# EV_SH.net
KiCad netlist of a schematic drawn in Altium Designer
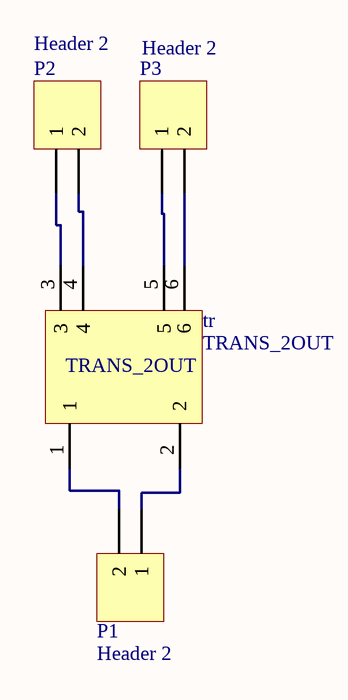
[diagram p0: EV_SH.SchDoc]

(export (version "E")
  (design (tool "Eeschema 10.0.6"))
  (components
    (comp (ref "P1")
      (value "Header 2")
      (footprint "HDR1X2")
      (description "Header, 2-Pin")
      (fields (field (name "PUBLISHER") "Altium Limited"))
      (libsource (lib "Miscellaneous Connectors") (part "Header 2"))
    )
    (comp (ref "P2")
      (value "Header 2")
      (footprint "HDR1X2")
      (description "Header, 2-Pin")
      (fields (field (name "PUBLISHER") "Altium Limited"))
      (libsource (lib "") (part "Header 2_1"))
    )
    (comp (ref "P3")
      (value "Header 2")
      (footprint "HDR1X2")
      (description "Header, 2-Pin")
      (fields (field (name "PUBLISHER") "Altium Limited"))
      (libsource (lib "") (part "Header 2_1"))
    )
    (comp (ref "tr")
      (value "TRANS_2OUT")
      (footprint "TRANS_2OUT")
      (libsource (lib "TRANS_LIB") (part "TRANS_2OUT"))
    )
  )
  (nets
    (net (code "1") (name "Net-(P1-Pad1)") (class "Default")
      (node (ref "P1") (pin "1") (pinfunction "1_1") (pintype "passive"))
      (node (ref "tr") (pin "2") (pinfunction "2_2") (pintype "passive"))
    )
    (net (code "2") (name "Net-(P1-Pad2)") (class "Default")
      (node (ref "P1") (pin "2") (pinfunction "2_2") (pintype "passive"))
      (node (ref "tr") (pin "1") (pinfunction "1_1") (pintype "passive"))
    )
    (net (code "3") (name "Net-(P2-Pad1)") (class "Default")
      (node (ref "P2") (pin "1") (pinfunction "1_1") (pintype "passive"))
      (node (ref "tr") (pin "3") (pinfunction "3_3") (pintype "passive"))
    )
    (net (code "4") (name "Net-(P2-Pad2)") (class "Default")
      (node (ref "P2") (pin "2") (pinfunction "2_2") (pintype "passive"))
      (node (ref "tr") (pin "4") (pinfunction "4_4") (pintype "passive"))
    )
    (net (code "5") (name "Net-(P3-Pad1)") (class "Default")
      (node (ref "P3") (pin "1") (pinfunction "1_1") (pintype "passive"))
      (node (ref "tr") (pin "5") (pinfunction "5_5") (pintype "passive"))
    )
    (net (code "6") (name "Net-(P3-Pad2)") (class "Default")
      (node (ref "P3") (pin "2") (pinfunction "2_2") (pintype "passive"))
      (node (ref "tr") (pin "6") (pinfunction "6_6") (pintype "passive"))
    )
  )
)
